# fpga_misc.net
KiCad netlist of a schematic drawn in Altium Designer
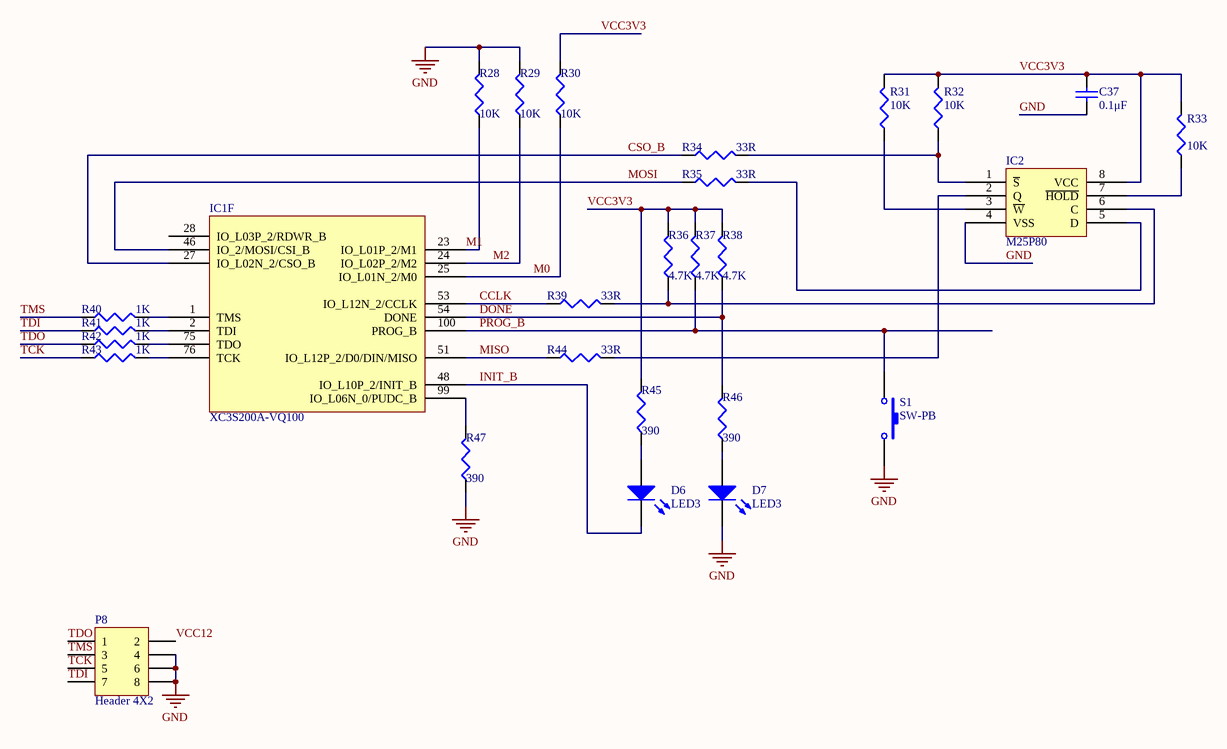
[diagram p0: fpga_misc.SchDoc]

(export (version "E")
  (design (tool "Eeschema 10.0.6"))
  (components
    (comp (ref "C37")
      (value "0.1μF")
      (footprint "1608[0603]")
      (description "Capacitor (Semiconductor SIM Model)")
      (fields (field (name "Comment") "Cap Semi") (field (name "PUBLISHER") "Altium Limited"))
      (libsource (lib "Miscellaneous Devices") (part "Cap Semi"))
    )
    (comp (ref "D6")
      (value "LED3")
      (footprint "LED0603")
      (description "Typical BLUE SiC LED")
      (fields (field (name "PUBLISHER") "Altium Limited"))
      (libsource (lib "Miscellaneous Devices") (part "LED3"))
    )
    (comp (ref "D7")
      (value "LED3")
      (footprint "LED0603")
      (description "Typical BLUE SiC LED")
      (fields (field (name "PUBLISHER") "Altium Limited"))
      (libsource (lib "Miscellaneous Devices") (part "LED3"))
    )
    (comp (ref "IC1")
      (value "XC3S200A-VQ100")
      (footprint "QFP50P1600X1600X120-100N")
      (libsource (lib "nir_usb") (part "XC3S200A-VQ100"))
    )
    (comp (ref "IC2") (value "M25P80") (footprint "SO8-WIDE8") (libsource (lib "nir_usb") (part "M25P80")))
    (comp (ref "P8")
      (value "Header 4X2")
      (footprint "HDR2X4")
      (description "Header, 4-Pin, Dual row")
      (fields (field (name "PUBLISHER") "Altium Limited"))
      (libsource (lib "Miscellaneous Connectors") (part "Header 4X2"))
    )
    (comp (ref "R28")
      (value "10K")
      (footprint "J1-0603")
      (description "Resistor")
      (fields (field (name "Comment") "Res3") (field (name "PUBLISHER") "Altium Limited"))
      (libsource (lib "Miscellaneous Devices") (part "Res3"))
    )
    (comp (ref "R29")
      (value "10K")
      (footprint "J1-0603")
      (description "Resistor")
      (fields (field (name "Comment") "Res3") (field (name "PUBLISHER") "Altium Limited"))
      (libsource (lib "Miscellaneous Devices") (part "Res3"))
    )
    (comp (ref "R30")
      (value "10K")
      (footprint "J1-0603")
      (description "Resistor")
      (fields (field (name "Comment") "Res3") (field (name "PUBLISHER") "Altium Limited"))
      (libsource (lib "Miscellaneous Devices") (part "Res3"))
    )
    (comp (ref "R31")
      (value "10K")
      (footprint "J1-0603")
      (description "Resistor")
      (fields (field (name "Comment") "Res3") (field (name "PUBLISHER") "Altium Limited"))
      (libsource (lib "Miscellaneous Devices") (part "Res3"))
    )
    (comp (ref "R32")
      (value "10K")
      (footprint "J1-0603")
      (description "Resistor")
      (fields (field (name "Comment") "Res3") (field (name "PUBLISHER") "Altium Limited"))
      (libsource (lib "Miscellaneous Devices") (part "Res3"))
    )
    (comp (ref "R33")
      (value "10K")
      (footprint "J1-0603")
      (description "Resistor")
      (fields (field (name "Comment") "Res3") (field (name "PUBLISHER") "Altium Limited"))
      (libsource (lib "Miscellaneous Devices") (part "Res3"))
    )
    (comp (ref "R34")
      (value "33R")
      (footprint "J1-0603")
      (description "Resistor")
      (fields (field (name "Comment") "Res3") (field (name "PUBLISHER") "Altium Limited"))
      (libsource (lib "Miscellaneous Devices") (part "Res3"))
    )
    (comp (ref "R35")
      (value "33R")
      (footprint "J1-0603")
      (description "Resistor")
      (fields (field (name "Comment") "Res3") (field (name "PUBLISHER") "Altium Limited"))
      (libsource (lib "Miscellaneous Devices") (part "Res3"))
    )
    (comp (ref "R36")
      (value "4.7K")
      (footprint "J1-0603")
      (description "Resistor")
      (fields (field (name "Comment") "Res3") (field (name "PUBLISHER") "Altium Limited"))
      (libsource (lib "Miscellaneous Devices") (part "Res3"))
    )
    (comp (ref "R37")
      (value "4.7K")
      (footprint "J1-0603")
      (description "Resistor")
      (fields (field (name "Comment") "Res3") (field (name "PUBLISHER") "Altium Limited"))
      (libsource (lib "Miscellaneous Devices") (part "Res3"))
    )
    (comp (ref "R38")
      (value "4.7K")
      (footprint "J1-0603")
      (description "Resistor")
      (fields (field (name "Comment") "Res3") (field (name "PUBLISHER") "Altium Limited"))
      (libsource (lib "Miscellaneous Devices") (part "Res3"))
    )
    (comp (ref "R39")
      (value "33R")
      (footprint "J1-0603")
      (description "Resistor")
      (fields (field (name "Comment") "Res3") (field (name "PUBLISHER") "Altium Limited"))
      (libsource (lib "Miscellaneous Devices") (part "Res3"))
    )
    (comp (ref "R40")
      (value "1K")
      (footprint "J1-0603")
      (description "Resistor")
      (fields (field (name "Comment") "Res3") (field (name "PUBLISHER") "Altium Limited"))
      (libsource (lib "Miscellaneous Devices") (part "Res3"))
    )
    (comp (ref "R41")
      (value "1K")
      (footprint "J1-0603")
      (description "Resistor")
      (fields (field (name "Comment") "Res3") (field (name "PUBLISHER") "Altium Limited"))
      (libsource (lib "Miscellaneous Devices") (part "Res3"))
    )
    (comp (ref "R42")
      (value "1K")
      (footprint "J1-0603")
      (description "Resistor")
      (fields (field (name "Comment") "Res3") (field (name "PUBLISHER") "Altium Limited"))
      (libsource (lib "Miscellaneous Devices") (part "Res3"))
    )
    (comp (ref "R43")
      (value "1K")
      (footprint "J1-0603")
      (description "Resistor")
      (fields (field (name "Comment") "Res3") (field (name "PUBLISHER") "Altium Limited"))
      (libsource (lib "Miscellaneous Devices") (part "Res3"))
    )
    (comp (ref "R44")
      (value "33R")
      (footprint "J1-0603")
      (description "Resistor")
      (fields (field (name "Comment") "Res3") (field (name "PUBLISHER") "Altium Limited"))
      (libsource (lib "Miscellaneous Devices") (part "Res3"))
    )
    (comp (ref "R45")
      (value "390")
      (footprint "J1-0603")
      (description "Resistor")
      (fields (field (name "Comment") "Res3") (field (name "PUBLISHER") "Altium Limited"))
      (libsource (lib "Miscellaneous Devices") (part "Res3"))
    )
    (comp (ref "R46")
      (value "390")
      (footprint "J1-0603")
      (description "Resistor")
      (fields (field (name "Comment") "Res3") (field (name "PUBLISHER") "Altium Limited"))
      (libsource (lib "Miscellaneous Devices") (part "Res3"))
    )
    (comp (ref "R47")
      (value "390")
      (footprint "J1-0603")
      (description "Resistor")
      (fields (field (name "Comment") "Res3") (field (name "PUBLISHER") "Altium Limited"))
      (libsource (lib "Miscellaneous Devices") (part "Res3"))
    )
    (comp (ref "S1")
      (value "SW-PB")
      (footprint "SPST-2")
      (description "Switch")
      (fields (field (name "PUBLISHER") "Altium Limited"))
      (libsource (lib "Miscellaneous Devices") (part "SW-PB"))
    )
  )
  (nets
    (net (code "1") (name "/CCLK") (class "Default")
      (node (ref "IC1") (pin "53") (pinfunction "IO_L12N_2/CCLK_53") (pintype "passive"))
      (node (ref "R39") (pin "1") (pinfunction "1_1") (pintype "passive"))
    )
    (net (code "2") (name "/CSO_B") (class "Default")
      (node (ref "IC1") (pin "27") (pinfunction "IO_L02N_2/CSO_B_27") (pintype "passive"))
      (node (ref "R34") (pin "1") (pinfunction "1_1") (pintype "passive"))
    )
    (net (code "3") (name "/DONE") (class "Default")
      (node (ref "IC1") (pin "54") (pinfunction "DONE_54") (pintype "passive"))
      (node (ref "R38") (pin "1") (pinfunction "1_1") (pintype "passive"))
      (node (ref "R46") (pin "2") (pinfunction "2_2") (pintype "passive"))
    )
    (net (code "4") (name "/INIT_B") (class "Default")
      (node (ref "D6") (pin "2") (pinfunction "K_2") (pintype "passive"))
      (node (ref "IC1") (pin "48") (pinfunction "IO_L10P_2/INIT_B_48") (pintype "passive"))
    )
    (net (code "5") (name "/M0") (class "Default")
      (node (ref "IC1") (pin "25") (pinfunction "IO_L01N_2/M0_25") (pintype "passive"))
      (node (ref "R30") (pin "1") (pinfunction "1_1") (pintype "passive"))
    )
    (net (code "6") (name "/M1") (class "Default")
      (node (ref "IC1") (pin "23") (pinfunction "IO_L01P_2/M1_23") (pintype "passive"))
      (node (ref "R28") (pin "1") (pinfunction "1_1") (pintype "passive"))
    )
    (net (code "7") (name "/M2") (class "Default")
      (node (ref "IC1") (pin "24") (pinfunction "IO_L02P_2/M2_24") (pintype "passive"))
      (node (ref "R29") (pin "1") (pinfunction "1_1") (pintype "passive"))
    )
    (net (code "8") (name "/MISO") (class "Default")
      (node (ref "IC1") (pin "51") (pinfunction "IO_L12P_2/D0/DIN/MISO_51") (pintype "passive"))
      (node (ref "R44") (pin "1") (pinfunction "1_1") (pintype "passive"))
    )
    (net (code "9") (name "/MOSI") (class "Default")
      (node (ref "IC1") (pin "46") (pinfunction "IO_2/MOSI/CSI_B_46") (pintype "passive"))
      (node (ref "R35") (pin "1") (pinfunction "1_1") (pintype "passive"))
    )
    (net (code "10") (name "/PROG_B") (class "Default")
      (node (ref "IC1") (pin "100") (pinfunction "PROG_B_100") (pintype "passive"))
      (node (ref "R37") (pin "1") (pinfunction "1_1") (pintype "passive"))
      (node (ref "S1") (pin "1") (pinfunction "1_1") (pintype "passive"))
    )
    (net (code "11") (name "/TCK") (class "Default")
      (node (ref "P8") (pin "5") (pinfunction "5_5") (pintype "passive"))
      (node (ref "R43") (pin "1") (pinfunction "1_1") (pintype "passive"))
    )
    (net (code "12") (name "/TDI") (class "Default")
      (node (ref "P8") (pin "7") (pinfunction "7_7") (pintype "passive"))
      (node (ref "R41") (pin "1") (pinfunction "1_1") (pintype "passive"))
    )
    (net (code "13") (name "/TDO") (class "Default")
      (node (ref "P8") (pin "1") (pinfunction "1_1") (pintype "passive"))
      (node (ref "R42") (pin "1") (pinfunction "1_1") (pintype "passive"))
    )
    (net (code "14") (name "/TMS") (class "Default")
      (node (ref "P8") (pin "3") (pinfunction "3_3") (pintype "passive"))
      (node (ref "R40") (pin "1") (pinfunction "1_1") (pintype "passive"))
    )
    (net (code "15") (name "/VCC3V3") (class "Default")
      (node (ref "C37") (pin "1") (pinfunction "1_1") (pintype "passive"))
      (node (ref "IC2") (pin "8") (pinfunction "VCC_8") (pintype "passive"))
      (node (ref "R30") (pin "2") (pinfunction "2_2") (pintype "passive"))
      (node (ref "R31") (pin "2") (pinfunction "2_2") (pintype "passive"))
      (node (ref "R32") (pin "2") (pinfunction "2_2") (pintype "passive"))
      (node (ref "R33") (pin "2") (pinfunction "2_2") (pintype "passive"))
      (node (ref "R36") (pin "2") (pinfunction "2_2") (pintype "passive"))
      (node (ref "R37") (pin "2") (pinfunction "2_2") (pintype "passive"))
      (node (ref "R38") (pin "2") (pinfunction "2_2") (pintype "passive"))
      (node (ref "R45") (pin "2") (pinfunction "2_2") (pintype "passive"))
    )
    (net (code "16") (name "/VCC12") (class "Default")
      (node (ref "P8") (pin "2") (pinfunction "2_2") (pintype "passive"))
    )
    (net (code "17") (name "GND") (class "Default")
      (node (ref "C37") (pin "2") (pinfunction "2_2") (pintype "passive"))
      (node (ref "D7") (pin "2") (pinfunction "K_2") (pintype "passive"))
      (node (ref "IC2") (pin "4") (pinfunction "VSS_4") (pintype "passive"))
      (node (ref "P8") (pin "4") (pinfunction "4_4") (pintype "passive"))
      (node (ref "P8") (pin "6") (pinfunction "6_6") (pintype "passive"))
      (node (ref "P8") (pin "8") (pinfunction "8_8") (pintype "passive"))
      (node (ref "R28") (pin "2") (pinfunction "2_2") (pintype "passive"))
      (node (ref "R29") (pin "2") (pinfunction "2_2") (pintype "passive"))
      (node (ref "R47") (pin "1") (pinfunction "1_1") (pintype "passive"))
      (node (ref "S1") (pin "2") (pinfunction "2_2") (pintype "passive"))
    )
    (net (code "18") (name "Net-(D6-A)") (class "Default")
      (node (ref "D6") (pin "1") (pinfunction "A_1") (pintype "passive"))
      (node (ref "R45") (pin "1") (pinfunction "1_1") (pintype "passive"))
    )
    (net (code "19") (name "Net-(D7-A)") (class "Default")
      (node (ref "D7") (pin "1") (pinfunction "A_1") (pintype "passive"))
      (node (ref "R46") (pin "1") (pinfunction "1_1") (pintype "passive"))
    )
    (net (code "20") (name "Net-(IC1F-IO_L06N_0{slash}PUDC_B)") (class "Default")
      (node (ref "IC1") (pin "99") (pinfunction "IO_L06N_0/PUDC_B_99") (pintype "passive"))
      (node (ref "R47") (pin "2") (pinfunction "2_2") (pintype "passive"))
    )
    (net (code "21") (name "Net-(IC1F-TCK)") (class "Default")
      (node (ref "IC1") (pin "76") (pinfunction "TCK_76") (pintype "passive"))
      (node (ref "R43") (pin "2") (pinfunction "2_2") (pintype "passive"))
    )
    (net (code "22") (name "Net-(IC1F-TDI)") (class "Default")
      (node (ref "IC1") (pin "2") (pinfunction "TDI_2") (pintype "passive"))
      (node (ref "R41") (pin "2") (pinfunction "2_2") (pintype "passive"))
    )
    (net (code "23") (name "Net-(IC1F-TDO)") (class "Default")
      (node (ref "IC1") (pin "75") (pinfunction "TDO_75") (pintype "passive"))
      (node (ref "R42") (pin "2") (pinfunction "2_2") (pintype "passive"))
    )
    (net (code "24") (name "Net-(IC1F-TMS)") (class "Default")
      (node (ref "IC1") (pin "1") (pinfunction "TMS_1") (pintype "passive"))
      (node (ref "R40") (pin "2") (pinfunction "2_2") (pintype "passive"))
    )
    (net (code "25") (name "Net-(IC2-C)") (class "Default")
      (node (ref "IC2") (pin "6") (pinfunction "C_6") (pintype "passive"))
      (node (ref "R36") (pin "1") (pinfunction "1_1") (pintype "passive"))
      (node (ref "R39") (pin "2") (pinfunction "2_2") (pintype "passive"))
    )
    (net (code "26") (name "Net-(IC2-D)") (class "Default")
      (node (ref "IC2") (pin "5") (pinfunction "D_5") (pintype "passive"))
      (node (ref "R35") (pin "2") (pinfunction "2_2") (pintype "passive"))
    )
    (net (code "27") (name "Net-(IC2-Q)") (class "Default")
      (node (ref "IC2") (pin "2") (pinfunction "Q_2") (pintype "passive"))
      (node (ref "R44") (pin "2") (pinfunction "2_2") (pintype "passive"))
    )
    (net (code "28") (name "Net-(IC2-~{HOLD})") (class "Default")
      (node (ref "IC2") (pin "7") (pinfunction "~{HOLD}_7") (pintype "passive"))
      (node (ref "R33") (pin "1") (pinfunction "1_1") (pintype "passive"))
    )
    (net (code "29") (name "Net-(IC2-~{S})") (class "Default")
      (node (ref "IC2") (pin "1") (pinfunction "~{S}_1") (pintype "passive"))
      (node (ref "R32") (pin "1") (pinfunction "1_1") (pintype "passive"))
      (node (ref "R34") (pin "2") (pinfunction "2_2") (pintype "passive"))
    )
    (net (code "30") (name "Net-(IC2-~{W})") (class "Default")
      (node (ref "IC2") (pin "3") (pinfunction "~{W}_3") (pintype "passive"))
      (node (ref "R31") (pin "1") (pinfunction "1_1") (pintype "passive"))
    )
    (net (code "31") (name "unconnected-(IC1F-IO_L03P_2{slash}RDWR_B-Pad28)") (class "Default")
      (node (ref "IC1") (pin "28") (pinfunction "IO_L03P_2/RDWR_B_28") (pintype "passive"))
    )
  )
)
